# LED_drv.net
KiCad netlist of a schematic drawn in EAGLE
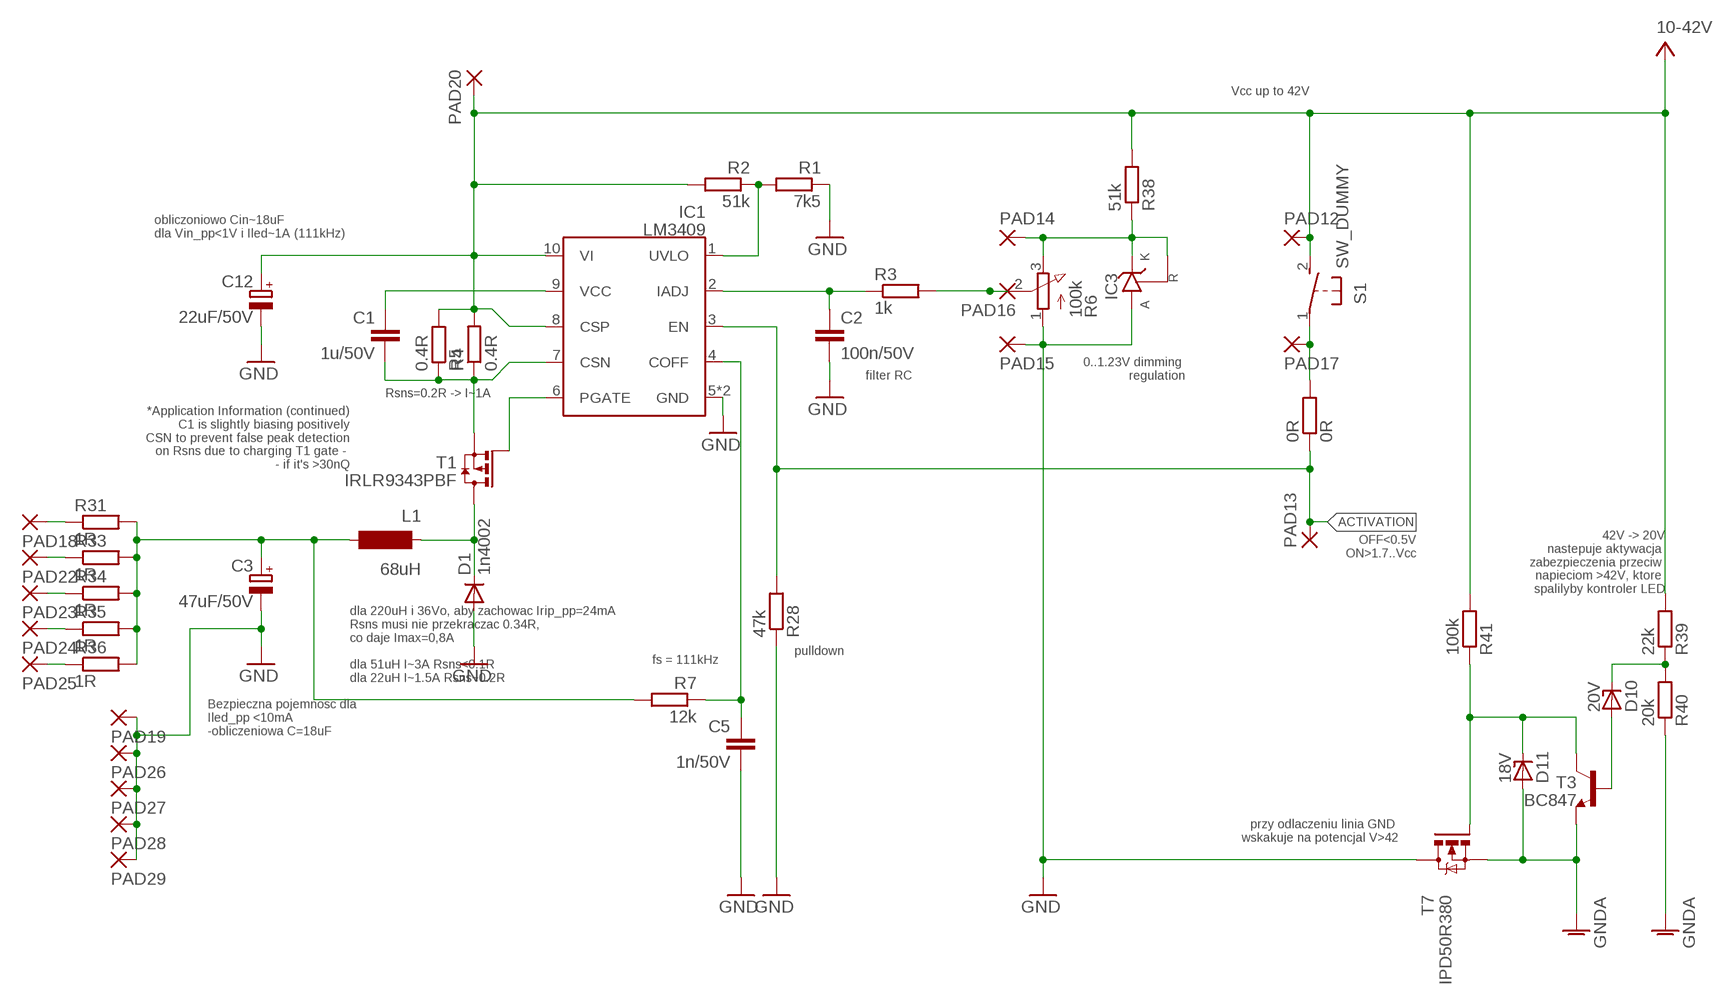
[diagram p0: schematic, sheet 1, part 1 of 2]
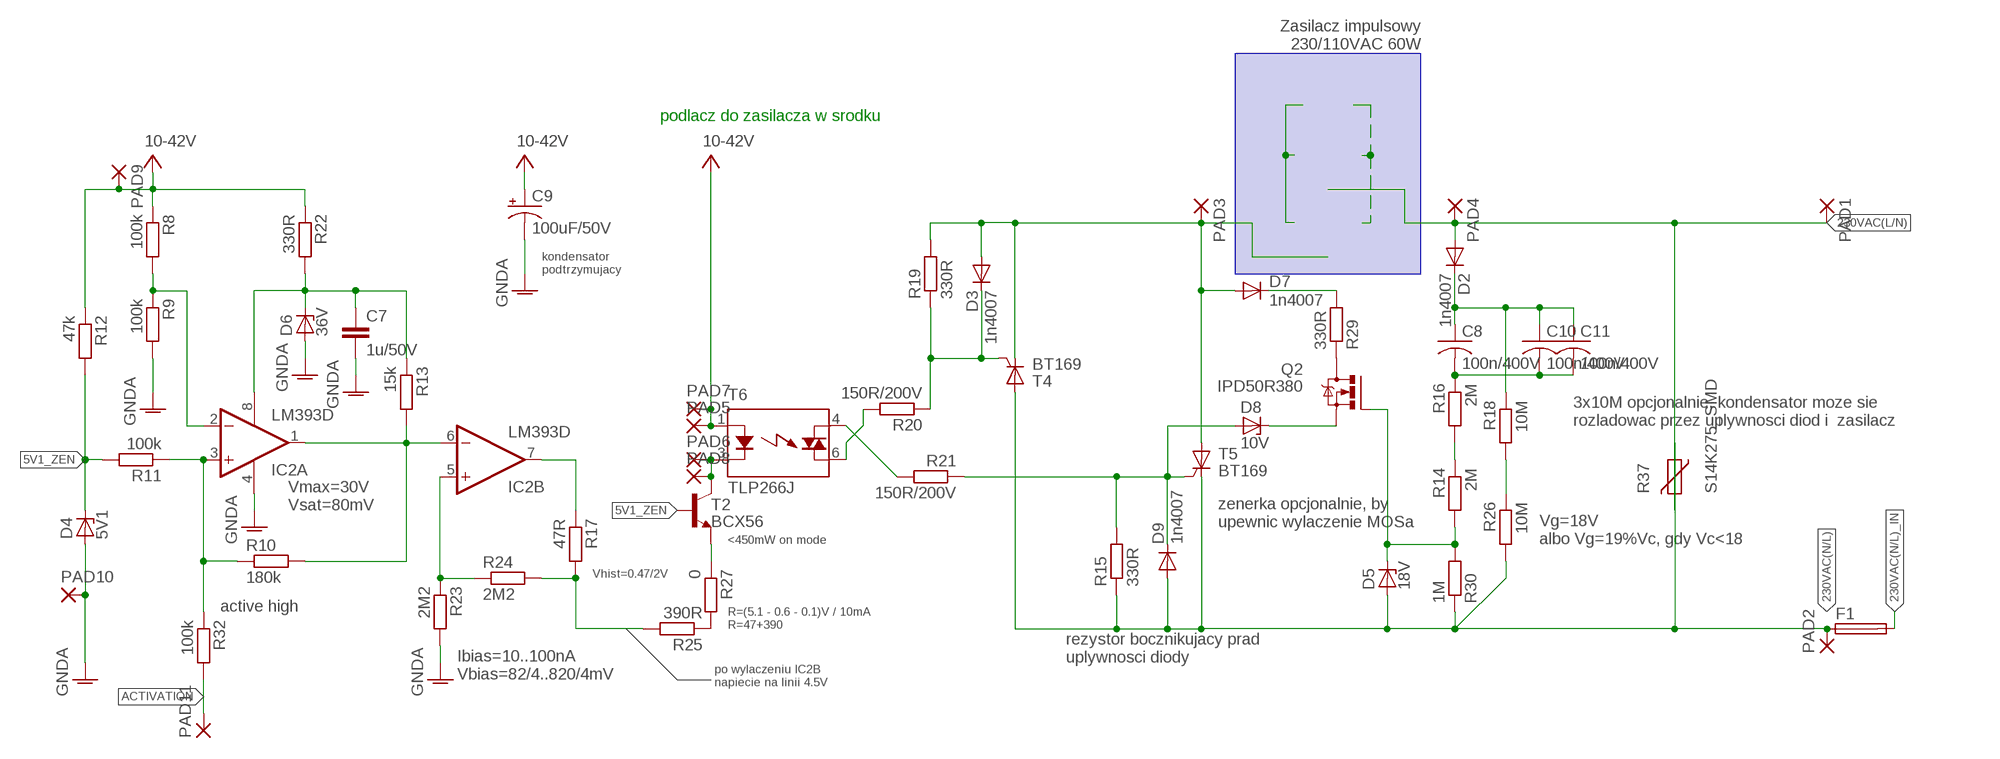
[diagram p1: schematic, sheet 1, part 2 of 2]

(export (version "E")
  (design (tool "Eeschema 10.0.6"))
  (components
    (comp (ref "0R")
      (value "0R")
      (footprint "eagle-import:R1206")
      (libsource (lib "eagle-import") (part "resistor_R-EU_R1206"))
    )
    (comp (ref "C1")
      (value "1u/50V")
      (footprint "eagle-import:C1206")
      (libsource (lib "eagle-import") (part "C-EUC1206"))
    )
    (comp (ref "C2")
      (value "100n/50V")
      (footprint "eagle-import:C0805")
      (libsource (lib "eagle-import") (part "C-EUC0805"))
    )
    (comp (ref "C3")
      (value "47uF/50V")
      (footprint "eagle-import:E5-6")
      (libsource (lib "eagle-import") (part "CPOL-EUE5-6"))
    )
    (comp (ref "C5")
      (value "1n/50V")
      (footprint "eagle-import:C0603")
      (libsource (lib "eagle-import") (part "C-EUC0603"))
    )
    (comp (ref "C7")
      (value "1u/50V")
      (footprint "eagle-import:C1206")
      (libsource (lib "eagle-import") (part "C-EUC1206"))
    )
    (comp (ref "C8")
      (value "100n/400V")
      (footprint "eagle-import:C075-032X103")
      (libsource (lib "eagle-import") (part "C-US075-032X103"))
    )
    (comp (ref "C9")
      (value "100uF/50V")
      (footprint "eagle-import:E3,5-8")
      (libsource (lib "eagle-import") (part "CPOL-USE3.5-8"))
    )
    (comp (ref "C10")
      (value "100n/400V")
      (footprint "eagle-import:C075-032X103")
      (libsource (lib "eagle-import") (part "C-US075-032X103"))
    )
    (comp (ref "C11")
      (value "100n/400V")
      (footprint "eagle-import:C075-032X103")
      (libsource (lib "eagle-import") (part "C-US075-032X103"))
    )
    (comp (ref "C12")
      (value "22uF/50V")
      (footprint "eagle-import:E5-6")
      (libsource (lib "eagle-import") (part "CPOL-EUE5-6"))
    )
    (comp (ref "D1")
      (value "1n4002")
      (footprint "eagle-import:DO214AC")
      (libsource (lib "eagle-import") (part "DIODE-DO214AC"))
    )
    (comp (ref "D2")
      (value "1n4007")
      (footprint "eagle-import:DO-214AC")
      (libsource (lib "eagle-import") (part "DIODE-DO-214AC"))
    )
    (comp (ref "D3")
      (value "1n4007")
      (footprint "eagle-import:DO-214AC")
      (libsource (lib "eagle-import") (part "DIODE-DO-214AC"))
    )
    (comp (ref "D4")
      (value "5V1")
      (footprint "eagle-import:SOD80C")
      (libsource (lib "eagle-import") (part "ZENER-DIODESOD80C"))
    )
    (comp (ref "D5")
      (value "18V")
      (footprint "eagle-import:SOD80C")
      (libsource (lib "eagle-import") (part "ZENER-DIODESOD80C"))
    )
    (comp (ref "D6")
      (value "36V")
      (footprint "eagle-import:SOD80C")
      (libsource (lib "eagle-import") (part "ZENER-DIODESOD80C"))
    )
    (comp (ref "D7")
      (value "1n4007")
      (footprint "eagle-import:DO-214AC")
      (libsource (lib "eagle-import") (part "DIODE-DO-214AC"))
    )
    (comp (ref "D8")
      (value "10V")
      (footprint "eagle-import:SOD80C")
      (libsource (lib "eagle-import") (part "ZENER-DIODESOD80C"))
    )
    (comp (ref "D9")
      (value "1n4007")
      (footprint "eagle-import:DO-214AC")
      (libsource (lib "eagle-import") (part "DIODE-DO-214AC"))
    )
    (comp (ref "D10")
      (value "20V")
      (footprint "eagle-import:SOD80C")
      (libsource (lib "eagle-import") (part "ZENER-DIODESOD80C"))
    )
    (comp (ref "D11")
      (value "18V")
      (footprint "eagle-import:SOD80C")
      (libsource (lib "eagle-import") (part "ZENER-DIODESOD80C"))
    )
    (comp (ref "F1")
      (value "SH22,5A")
      (footprint "eagle-import:SH22,5A")
      (fields (field (name "MPN") "0031.7701.11"))
      (libsource (lib "eagle-import") (part "SH22,5A"))
    )
    (comp (ref "IC1")
      (value "LM3409")
      (footprint "eagle-import:HVSSOP-10")
      (libsource (lib "eagle-import") (part "LM3409"))
    )
    (comp (ref "IC2")
      (value "LM393D")
      (footprint "eagle-import:SO08")
      (libsource (lib "eagle-import") (part "LM393D"))
    )
    (comp (ref "IC3")
      (value "TL431-ASA")
      (footprint "eagle-import:SOT23-3")
      (libsource (lib "eagle-import") (part "TL431-ASA"))
    )
    (comp (ref "L1")
      (value "68uH")
      (footprint "eagle-import:CDRH104-R")
      (libsource (lib "eagle-import") (part "CDRH104R"))
    )
    (comp (ref "PAD1")
      (value "SMD5")
      (footprint "eagle-import:SMD2,54-5,08")
      (libsource (lib "eagle-import") (part "SMD5"))
    )
    (comp (ref "PAD2")
      (value "SMD5")
      (footprint "eagle-import:SMD2,54-5,08")
      (libsource (lib "eagle-import") (part "SMD5"))
    )
    (comp (ref "PAD3")
      (value "SMD5")
      (footprint "eagle-import:SMD2,54-5,08")
      (libsource (lib "eagle-import") (part "SMD5"))
    )
    (comp (ref "PAD4")
      (value "SMD5")
      (footprint "eagle-import:SMD2,54-5,08")
      (libsource (lib "eagle-import") (part "SMD5"))
    )
    (comp (ref "PAD5")
      (value "SMD2")
      (footprint "eagle-import:SMD1,27-2,54")
      (libsource (lib "eagle-import") (part "SMD2"))
    )
    (comp (ref "PAD6")
      (value "SMD2")
      (footprint "eagle-import:SMD1,27-2,54")
      (libsource (lib "eagle-import") (part "SMD2"))
    )
    (comp (ref "PAD7")
      (value "SMD2")
      (footprint "eagle-import:SMD1,27-2,54")
      (libsource (lib "eagle-import") (part "SMD2"))
    )
    (comp (ref "PAD8")
      (value "SMD2")
      (footprint "eagle-import:SMD1,27-2,54")
      (libsource (lib "eagle-import") (part "SMD2"))
    )
    (comp (ref "PAD9")
      (value "SMD2")
      (footprint "eagle-import:SMD1,27-2,54")
      (libsource (lib "eagle-import") (part "SMD2"))
    )
    (comp (ref "PAD10")
      (value "SMD2")
      (footprint "eagle-import:SMD1,27-2,54")
      (libsource (lib "eagle-import") (part "SMD2"))
    )
    (comp (ref "PAD11")
      (value "SMD2")
      (footprint "eagle-import:SMD1,27-2,54")
      (libsource (lib "eagle-import") (part "SMD2"))
    )
    (comp (ref "PAD12")
      (value "SMD2")
      (footprint "eagle-import:SMD1,27-2,54")
      (libsource (lib "eagle-import") (part "SMD2"))
    )
    (comp (ref "PAD13")
      (value "SMD2")
      (footprint "eagle-import:SMD1,27-2,54")
      (libsource (lib "eagle-import") (part "SMD2"))
    )
    (comp (ref "PAD14")
      (value "SMD2")
      (footprint "eagle-import:SMD1,27-2,54")
      (libsource (lib "eagle-import") (part "SMD2"))
    )
    (comp (ref "PAD15")
      (value "SMD2")
      (footprint "eagle-import:SMD1,27-2,54")
      (libsource (lib "eagle-import") (part "SMD2"))
    )
    (comp (ref "PAD16")
      (value "SMD2")
      (footprint "eagle-import:SMD1,27-2,54")
      (libsource (lib "eagle-import") (part "SMD2"))
    )
    (comp (ref "PAD17")
      (value "SMD2")
      (footprint "eagle-import:SMD1,27-2,54")
      (libsource (lib "eagle-import") (part "SMD2"))
    )
    (comp (ref "PAD18")
      (value "SMD2")
      (footprint "eagle-import:SMD1,27-2,54")
      (libsource (lib "eagle-import") (part "SMD2"))
    )
    (comp (ref "PAD19")
      (value "SMD2")
      (footprint "eagle-import:SMD1,27-2,54")
      (libsource (lib "eagle-import") (part "SMD2"))
    )
    (comp (ref "PAD20")
      (value "SMD2")
      (footprint "eagle-import:SMD1,27-2,54")
      (libsource (lib "eagle-import") (part "SMD2"))
    )
    (comp (ref "PAD22")
      (value "SMD2")
      (footprint "eagle-import:SMD1,27-2,54")
      (libsource (lib "eagle-import") (part "SMD2"))
    )
    (comp (ref "PAD23")
      (value "SMD2")
      (footprint "eagle-import:SMD1,27-2,54")
      (libsource (lib "eagle-import") (part "SMD2"))
    )
    (comp (ref "PAD24")
      (value "SMD2")
      (footprint "eagle-import:SMD1,27-2,54")
      (libsource (lib "eagle-import") (part "SMD2"))
    )
    (comp (ref "PAD25")
      (value "SMD2")
      (footprint "eagle-import:SMD1,27-2,54")
      (libsource (lib "eagle-import") (part "SMD2"))
    )
    (comp (ref "PAD26")
      (value "SMD2")
      (footprint "eagle-import:SMD1,27-2,54")
      (libsource (lib "eagle-import") (part "SMD2"))
    )
    (comp (ref "PAD27")
      (value "SMD2")
      (footprint "eagle-import:SMD1,27-2,54")
      (libsource (lib "eagle-import") (part "SMD2"))
    )
    (comp (ref "PAD28")
      (value "SMD2")
      (footprint "eagle-import:SMD1,27-2,54")
      (libsource (lib "eagle-import") (part "SMD2"))
    )
    (comp (ref "PAD29")
      (value "SMD2")
      (footprint "eagle-import:SMD1,27-2,54")
      (libsource (lib "eagle-import") (part "SMD2"))
    )
    (comp (ref "Q2")
      (value "IPD50R380")
      (footprint "eagle-import:TO252-3-11")
      (libsource (lib "eagle-import") (part "IPD50R380"))
    )
    (comp (ref "R1")
      (value "7k5")
      (footprint "eagle-import:R1206")
      (libsource (lib "eagle-import") (part "R-EU_R1206"))
    )
    (comp (ref "R2")
      (value "51k")
      (footprint "eagle-import:R1206")
      (libsource (lib "eagle-import") (part "R-EU_R1206"))
    )
    (comp (ref "R3")
      (value "1k")
      (footprint "eagle-import:R0805")
      (libsource (lib "eagle-import") (part "R-EU_R0805"))
    )
    (comp (ref "R4")
      (value "0.4R")
      (footprint "eagle-import:R1206")
      (libsource (lib "eagle-import") (part "resistor_R-EU_R1206"))
    )
    (comp (ref "R5")
      (value "0.4R")
      (footprint "eagle-import:R1206")
      (libsource (lib "eagle-import") (part "resistor_R-EU_R1206"))
    )
    (comp (ref "R6")
      (value "100k")
      (footprint "eagle-import:3RP_1610N")
      (libsource (lib "eagle-import") (part "3RP/1610N"))
    )
    (comp (ref "R7")
      (value "12k")
      (footprint "eagle-import:R1206")
      (libsource (lib "eagle-import") (part "R-EU_R1206"))
    )
    (comp (ref "R8")
      (value "100k")
      (footprint "eagle-import:R0805")
      (libsource (lib "eagle-import") (part "resistor_R-EU_R0805"))
    )
    (comp (ref "R9")
      (value "100k")
      (footprint "eagle-import:R1206")
      (libsource (lib "eagle-import") (part "R-EU_R1206"))
    )
    (comp (ref "R10")
      (value "180k")
      (footprint "eagle-import:R1206")
      (libsource (lib "eagle-import") (part "R-EU_R1206"))
    )
    (comp (ref "R11")
      (value "100k")
      (footprint "eagle-import:R0805")
      (libsource (lib "eagle-import") (part "resistor_R-EU_R0805"))
    )
    (comp (ref "R12")
      (value "47k")
      (footprint "eagle-import:R0805")
      (libsource (lib "eagle-import") (part "resistor_R-EU_R0805"))
    )
    (comp (ref "R13")
      (value "15k")
      (footprint "eagle-import:R0805")
      (libsource (lib "eagle-import") (part "resistor_R-EU_R0805"))
    )
    (comp (ref "R14")
      (value "2M")
      (footprint "eagle-import:R1206")
      (libsource (lib "eagle-import") (part "R-EU_R1206"))
    )
    (comp (ref "R15")
      (value "330R")
      (footprint "eagle-import:R1206")
      (libsource (lib "eagle-import") (part "R-EU_R1206"))
    )
    (comp (ref "R16")
      (value "2M")
      (footprint "eagle-import:R1206")
      (libsource (lib "eagle-import") (part "R-EU_R1206"))
    )
    (comp (ref "R17")
      (value "47R")
      (footprint "eagle-import:R0805")
      (libsource (lib "eagle-import") (part "resistor_R-EU_R0805"))
    )
    (comp (ref "R18")
      (value "10M")
      (footprint "eagle-import:R1206")
      (libsource (lib "eagle-import") (part "R-EU_R1206"))
    )
    (comp (ref "R19")
      (value "330R")
      (footprint "eagle-import:R1206")
      (libsource (lib "eagle-import") (part "R-EU_R1206"))
    )
    (comp (ref "R20")
      (value "150R/200V")
      (footprint "eagle-import:R1206")
      (libsource (lib "eagle-import") (part "R-EU_R1206"))
    )
    (comp (ref "R21")
      (value "150R/200V")
      (footprint "eagle-import:R1206")
      (libsource (lib "eagle-import") (part "R-EU_R1206"))
    )
    (comp (ref "R22")
      (value "330R")
      (footprint "eagle-import:R0805")
      (libsource (lib "eagle-import") (part "resistor_R-EU_R0805"))
    )
    (comp (ref "R23")
      (value "2M2")
      (footprint "eagle-import:R0805")
      (libsource (lib "eagle-import") (part "resistor_R-EU_R0805"))
    )
    (comp (ref "R24")
      (value "2M2")
      (footprint "eagle-import:R0805")
      (libsource (lib "eagle-import") (part "resistor_R-EU_R0805"))
    )
    (comp (ref "R25")
      (value "390R")
      (footprint "eagle-import:R0805")
      (libsource (lib "eagle-import") (part "resistor_R-EU_R0805"))
    )
    (comp (ref "R26")
      (value "10M")
      (footprint "eagle-import:R1206")
      (libsource (lib "eagle-import") (part "R-EU_R1206"))
    )
    (comp (ref "R27")
      (value "0")
      (footprint "eagle-import:R1206")
      (libsource (lib "eagle-import") (part "R-EU_R1206"))
    )
    (comp (ref "R28")
      (value "47k")
      (footprint "eagle-import:R0805")
      (libsource (lib "eagle-import") (part "R-EU_R0805"))
    )
    (comp (ref "R29")
      (value "330R")
      (footprint "eagle-import:R1206")
      (libsource (lib "eagle-import") (part "R-EU_R1206"))
    )
    (comp (ref "R30")
      (value "1M")
      (footprint "eagle-import:R1206")
      (libsource (lib "eagle-import") (part "R-EU_R1206"))
    )
    (comp (ref "R31")
      (value "1R")
      (footprint "eagle-import:R1206")
      (libsource (lib "eagle-import") (part "resistor_R-EU_R1206"))
    )
    (comp (ref "R32")
      (value "100k")
      (footprint "eagle-import:R0805")
      (libsource (lib "eagle-import") (part "resistor_R-EU_R0805"))
    )
    (comp (ref "R33")
      (value "1R")
      (footprint "eagle-import:R1206")
      (libsource (lib "eagle-import") (part "resistor_R-EU_R1206"))
    )
    (comp (ref "R34")
      (value "1R")
      (footprint "eagle-import:R1206")
      (libsource (lib "eagle-import") (part "resistor_R-EU_R1206"))
    )
    (comp (ref "R35")
      (value "1R")
      (footprint "eagle-import:R1206")
      (libsource (lib "eagle-import") (part "resistor_R-EU_R1206"))
    )
    (comp (ref "R36")
      (value "1R")
      (footprint "eagle-import:R1206")
      (libsource (lib "eagle-import") (part "resistor_R-EU_R1206"))
    )
    (comp (ref "R37")
      (value "S14K275_SMD")
      (footprint "eagle-import:S14K275_SMD")
      (libsource (lib "eagle-import") (part "S14K275_SMD"))
    )
    (comp (ref "R38")
      (value "51k")
      (footprint "eagle-import:R1206")
      (libsource (lib "eagle-import") (part "R-EU_R1206"))
    )
    (comp (ref "R39")
      (value "22k")
      (footprint "eagle-import:R1206")
      (libsource (lib "eagle-import") (part "R-EU_R1206"))
    )
    (comp (ref "R40")
      (value "20k")
      (footprint "eagle-import:R1206")
      (libsource (lib "eagle-import") (part "R-EU_R1206"))
    )
    (comp (ref "R41")
      (value "100k")
      (footprint "eagle-import:R1206")
      (libsource (lib "eagle-import") (part "R-EU_R1206"))
    )
    (comp (ref "S1")
      (value "SW_DUMMY")
      (footprint "eagle-import:SW_DUMMY")
      (libsource (lib "eagle-import") (part "SW_DUMMY"))
    )
    (comp (ref "T1")
      (value "IRLR9343PBF")
      (footprint "eagle-import:TO252-3-11")
      (libsource (lib "eagle-import") (part "IRLR9343PBF"))
    )
    (comp (ref "T2")
      (value "BCX56")
      (footprint "eagle-import:SOT89")
      (libsource (lib "eagle-import") (part "BCX56"))
    )
    (comp (ref "T3")
      (value "BC847")
      (footprint "eagle-import:SOT23")
      (libsource (lib "eagle-import") (part "BC847"))
    )
    (comp (ref "T4")
      (value "BT169")
      (footprint "eagle-import:SOT223")
      (libsource (lib "eagle-import") (part "BT169"))
    )
    (comp (ref "T5")
      (value "BT169")
      (footprint "eagle-import:SOT223")
      (libsource (lib "eagle-import") (part "BT169"))
    )
    (comp (ref "T6")
      (value "TLP266J")
      (footprint "eagle-import:SO6")
      (libsource (lib "eagle-import") (part "TLP266J"))
    )
    (comp (ref "T7")
      (value "IPD50R380")
      (footprint "eagle-import:TO252-3-11")
      (libsource (lib "eagle-import") (part "IPD50R380"))
    )
  )
  (nets
    (net (code "1") (name "5V1_ZEN") (class "Default")
      (node (ref "D4") (pin "C") (pinfunction "C_C") (pintype "passive"))
      (node (ref "R11") (pin "2") (pinfunction "2_2") (pintype "passive"))
      (node (ref "R12") (pin "2") (pinfunction "2_2") (pintype "passive"))
      (node (ref "T2") (pin "B") (pinfunction "B_B") (pintype "passive"))
    )
    (net (code "2") (name "10-42V") (class "Default")
      (node (ref "C12") (pin "+") (pinfunction "+_+") (pintype "passive"))
      (node (ref "C9") (pin "+") (pinfunction "+_+") (pintype "passive"))
      (node (ref "IC1") (pin "10") (pinfunction "VI_10") (pintype "output"))
      (node (ref "IC1") (pin "8") (pinfunction "CSP_8") (pintype "passive"))
      (node (ref "PAD12") (pin "1") (pinfunction "P_1") (pintype "passive"))
      (node (ref "PAD20") (pin "1") (pinfunction "P_1") (pintype "passive"))
      (node (ref "PAD5") (pin "1") (pinfunction "P_1") (pintype "passive"))
      (node (ref "PAD7") (pin "1") (pinfunction "P_1") (pintype "passive"))
      (node (ref "PAD9") (pin "1") (pinfunction "P_1") (pintype "passive"))
      (node (ref "R12") (pin "1") (pinfunction "1_1") (pintype "passive"))
      (node (ref "R2") (pin "2") (pinfunction "2_2") (pintype "passive"))
      (node (ref "R22") (pin "1") (pinfunction "1_1") (pintype "passive"))
      (node (ref "R38") (pin "2") (pinfunction "2_2") (pintype "passive"))
      (node (ref "R39") (pin "2") (pinfunction "2_2") (pintype "passive"))
      (node (ref "R4") (pin "2") (pinfunction "2_2") (pintype "passive"))
      (node (ref "R41") (pin "2") (pinfunction "2_2") (pintype "passive"))
      (node (ref "R5") (pin "2") (pinfunction "2_2") (pintype "passive"))
      (node (ref "R8") (pin "1") (pinfunction "1_1") (pintype "passive"))
      (node (ref "S1") (pin "2") (pinfunction "S_2") (pintype "passive"))
      (node (ref "T6") (pin "1") (pinfunction "A_1") (pintype "passive"))
    )
    (net (code "3") (name "230VAC(L{slash}N)") (class "Default")
      (node (ref "D2") (pin "A") (pinfunction "A_A") (pintype "passive"))
      (node (ref "PAD1") (pin "1") (pinfunction "P_1") (pintype "passive"))
      (node (ref "PAD4") (pin "1") (pinfunction "P_1") (pintype "passive"))
      (node (ref "R37") (pin "2") (pinfunction "2_2") (pintype "passive"))
    )
    (net (code "4") (name "230VAC(N{slash}L)") (class "Default")
      (node (ref "D5") (pin "A") (pinfunction "A_A") (pintype "passive"))
      (node (ref "D9") (pin "A") (pinfunction "A_A") (pintype "passive"))
      (node (ref "F1") (pin "1") (pinfunction "1_1") (pintype "passive"))
      (node (ref "PAD2") (pin "1") (pinfunction "P_1") (pintype "passive"))
      (node (ref "R15") (pin "1") (pinfunction "1_1") (pintype "passive"))
      (node (ref "R26") (pin "2") (pinfunction "2_2") (pintype "passive"))
      (node (ref "R30") (pin "1") (pinfunction "1_1") (pintype "passive"))
      (node (ref "R37") (pin "1") (pinfunction "1_1") (pintype "passive"))
      (node (ref "T4") (pin "2") (pinfunction "A_2") (pintype "passive"))
      (node (ref "T4") (pin "4") (pinfunction "A_4") (pintype "passive"))
      (node (ref "T5") (pin "3") (pinfunction "C_3") (pintype "passive"))
    )
    (net (code "5") (name "230VAC(N{slash}L)_IN") (class "Default")
      (node (ref "F1") (pin "2") (pinfunction "2_2") (pintype "passive"))
    )
    (net (code "6") (name "ACTIVATION") (class "Default")
      (node (ref "0R") (pin "1") (pinfunction "1_1") (pintype "passive"))
      (node (ref "IC1") (pin "3") (pinfunction "EN_3") (pintype "power_in"))
      (node (ref "PAD11") (pin "1") (pinfunction "P_1") (pintype "passive"))
      (node (ref "PAD13") (pin "1") (pinfunction "P_1") (pintype "passive"))
      (node (ref "R28") (pin "2") (pinfunction "2_2") (pintype "passive"))
      (node (ref "R32") (pin "2") (pinfunction "2_2") (pintype "passive"))
    )
    (net (code "7") (name "GND") (class "Default")
      (node (ref "C12") (pin "-") (pinfunction "-_-") (pintype "passive"))
      (node (ref "C2") (pin "2") (pinfunction "2_2") (pintype "passive"))
      (node (ref "C3") (pin "-") (pinfunction "-_-") (pintype "passive"))
      (node (ref "C5") (pin "2") (pinfunction "2_2") (pintype "passive"))
      (node (ref "D1") (pin "A") (pinfunction "A_A") (pintype "passive"))
      (node (ref "IC1") (pin "5") (pinfunction "GND_5") (pintype "bidirectional"))
      (node (ref "IC1") (pin "EXT") (pinfunction "GND_EXT") (pintype "bidirectional"))
      (node (ref "IC3") (pin "3") (pinfunction "A_3") (pintype "bidirectional"))
      (node (ref "PAD15") (pin "1") (pinfunction "P_1") (pintype "passive"))
      (node (ref "PAD19") (pin "1") (pinfunction "P_1") (pintype "passive"))
      (node (ref "PAD26") (pin "1") (pinfunction "P_1") (pintype "passive"))
      (node (ref "PAD27") (pin "1") (pinfunction "P_1") (pintype "passive"))
      (node (ref "PAD28") (pin "1") (pinfunction "P_1") (pintype "passive"))
      (node (ref "PAD29") (pin "1") (pinfunction "P_1") (pintype "passive"))
      (node (ref "R1") (pin "1") (pinfunction "1_1") (pintype "passive"))
      (node (ref "R28") (pin "1") (pinfunction "1_1") (pintype "passive"))
      (node (ref "R6") (pin "1") (pinfunction "A_1") (pintype "passive"))
      (node (ref "T7") (pin "2") (pinfunction "D_2") (pintype "passive"))
    )
    (net (code "8") (name "GNDA") (class "Default")
      (node (ref "C7") (pin "2") (pinfunction "2_2") (pintype "passive"))
      (node (ref "C9") (pin "-") (pinfunction "-_-") (pintype "passive"))
      (node (ref "D11") (pin "A") (pinfunction "A_A") (pintype "passive"))
      (node (ref "D4") (pin "A") (pinfunction "A_A") (pintype "passive"))
      (node (ref "D6") (pin "A") (pinfunction "A_A") (pintype "passive"))
      (node (ref "IC2") (pin "4") (pinfunction "V-_4") (pintype "power_in"))
      (node (ref "PAD10") (pin "1") (pinfunction "P_1") (pintype "passive"))
      (node (ref "R23") (pin "2") (pinfunction "2_2") (pintype "passive"))
      (node (ref "R40") (pin "1") (pinfunction "1_1") (pintype "passive"))
      (node (ref "R9") (pin "2") (pinfunction "2_2") (pintype "passive"))
      (node (ref "T3") (pin "2") (pinfunction "E_2") (pintype "passive"))
      (node (ref "T7") (pin "3") (pinfunction "S_3") (pintype "passive"))
    )
    (net (code "9") (name "Net-(C3-Pad+)") (class "Default")
      (node (ref "C3") (pin "+") (pinfunction "+_+") (pintype "passive"))
      (node (ref "L1") (pin "2") (pinfunction "2_2") (pintype "passive"))
      (node (ref "R31") (pin "2") (pinfunction "2_2") (pintype "passive"))
      (node (ref "R33") (pin "2") (pinfunction "2_2") (pintype "passive"))
      (node (ref "R34") (pin "2") (pinfunction "2_2") (pintype "passive"))
      (node (ref "R35") (pin "2") (pinfunction "2_2") (pintype "passive"))
      (node (ref "R36") (pin "2") (pinfunction "2_2") (pintype "passive"))
      (node (ref "R7") (pin "2") (pinfunction "2_2") (pintype "passive"))
    )
    (net (code "10") (name "Net-(C10-Pad1)") (class "Default")
      (node (ref "C10") (pin "1") (pinfunction "1_1") (pintype "passive"))
      (node (ref "C11") (pin "1") (pinfunction "1_1") (pintype "passive"))
      (node (ref "C8") (pin "1") (pinfunction "1_1") (pintype "passive"))
      (node (ref "D2") (pin "C") (pinfunction "C_C") (pintype "passive"))
      (node (ref "R18") (pin "1") (pinfunction "1_1") (pintype "passive"))
    )
    (net (code "11") (name "Net-(C10-Pad2)") (class "Default")
      (node (ref "C10") (pin "2") (pinfunction "2_2") (pintype "passive"))
      (node (ref "C11") (pin "2") (pinfunction "2_2") (pintype "passive"))
      (node (ref "C8") (pin "2") (pinfunction "2_2") (pintype "passive"))
      (node (ref "R16") (pin "1") (pinfunction "1_1") (pintype "passive"))
    )
    (net (code "12") (name "Net-(D7-PadC)") (class "Default")
      (node (ref "D7") (pin "C") (pinfunction "C_C") (pintype "passive"))
      (node (ref "R29") (pin "2") (pinfunction "2_2") (pintype "passive"))
    )
    (net (code "13") (name "Net-(D10-PadC)") (class "Default")
      (node (ref "D10") (pin "C") (pinfunction "C_C") (pintype "passive"))
      (node (ref "R39") (pin "1") (pinfunction "1_1") (pintype "passive"))
      (node (ref "R40") (pin "2") (pinfunction "2_2") (pintype "passive"))
    )
    (net (code "14") (name "Net-(IC1-COFF)") (class "Default")
      (node (ref "C5") (pin "1") (pinfunction "1_1") (pintype "passive"))
      (node (ref "IC1") (pin "4") (pinfunction "COFF_4") (pintype "power_in"))
      (node (ref "R7") (pin "1") (pinfunction "1_1") (pintype "passive"))
    )
    (net (code "15") (name "Net-(IC1-CSN)") (class "Default")
      (node (ref "C1") (pin "2") (pinfunction "2_2") (pintype "passive"))
      (node (ref "IC1") (pin "7") (pinfunction "CSN_7") (pintype "passive"))
      (node (ref "R4") (pin "1") (pinfunction "1_1") (pintype "passive"))
      (node (ref "R5") (pin "1") (pinfunction "1_1") (pintype "passive"))
      (node (ref "T1") (pin "2") (pinfunction "S_2") (pintype "passive"))
    )
    (net (code "16") (name "Net-(IC1-IADJ)") (class "Default")
      (node (ref "C2") (pin "1") (pinfunction "1_1") (pintype "passive"))
      (node (ref "IC1") (pin "2") (pinfunction "IADJ_2") (pintype "input"))
      (node (ref "R3") (pin "1") (pinfunction "1_1") (pintype "passive"))
    )
    (net (code "17") (name "Net-(IC1-PGATE)") (class "Default")
      (node (ref "IC1") (pin "6") (pinfunction "PGATE_6") (pintype "bidirectional"))
      (node (ref "T1") (pin "1") (pinfunction "G_1") (pintype "passive"))
    )
    (net (code "18") (name "Net-(IC1-UVLO)") (class "Default")
      (node (ref "IC1") (pin "1") (pinfunction "UVLO_1") (pintype "input"))
      (node (ref "R1") (pin "2") (pinfunction "2_2") (pintype "passive"))
      (node (ref "R2") (pin "1") (pinfunction "1_1") (pintype "passive"))
    )
    (net (code "19") (name "Net-(IC1-VCC)") (class "Default")
      (node (ref "C1") (pin "1") (pinfunction "1_1") (pintype "passive"))
      (node (ref "IC1") (pin "9") (pinfunction "VCC_9") (pintype "passive"))
    )
    (net (code "20") (name "Net-(IC2A-+IN)") (class "Default")
      (node (ref "IC2") (pin "3") (pinfunction "+IN_3") (pintype "input"))
      (node (ref "R10") (pin "1") (pinfunction "1_1") (pintype "passive"))
      (node (ref "R11") (pin "1") (pinfunction "1_1") (pintype "passive"))
      (node (ref "R32") (pin "1") (pinfunction "1_1") (pintype "passive"))
    )
    (net (code "21") (name "Net-(IC2A--IN)") (class "Default")
      (node (ref "IC2") (pin "2") (pinfunction "-IN_2") (pintype "input"))
      (node (ref "R8") (pin "2") (pinfunction "2_2") (pintype "passive"))
      (node (ref "R9") (pin "1") (pinfunction "1_1") (pintype "passive"))
    )
    (net (code "22") (name "Net-(IC2A-OUT)") (class "Default")
      (node (ref "IC2") (pin "1") (pinfunction "OUT_1") (pintype "output"))
      (node (ref "IC2") (pin "6") (pinfunction "-IN_6") (pintype "input"))
      (node (ref "R10") (pin "2") (pinfunction "2_2") (pintype "passive"))
      (node (ref "R13") (pin "2") (pinfunction "2_2") (pintype "passive"))
    )
    (net (code "23") (name "Net-(IC2B-+IN)") (class "Default")
      (node (ref "IC2") (pin "5") (pinfunction "+IN_5") (pintype "input"))
      (node (ref "R23") (pin "1") (pinfunction "1_1") (pintype "passive"))
      (node (ref "R24") (pin "1") (pinfunction "1_1") (pintype "passive"))
    )
    (net (code "24") (name "Net-(IC2B-OUT)") (class "Default")
      (node (ref "IC2") (pin "7") (pinfunction "OUT_7") (pintype "output"))
      (node (ref "R17") (pin "1") (pinfunction "1_1") (pintype "passive"))
    )
    (net (code "25") (name "Net-(IC2C-V+)") (class "Default")
      (node (ref "C7") (pin "1") (pinfunction "1_1") (pintype "passive"))
      (node (ref "D6") (pin "C") (pinfunction "C_C") (pintype "passive"))
      (node (ref "IC2") (pin "8") (pinfunction "V+_8") (pintype "power_in"))
      (node (ref "R13") (pin "1") (pinfunction "1_1") (pintype "passive"))
      (node (ref "R22") (pin "2") (pinfunction "2_2") (pintype "passive"))
    )
    (net (code "26") (name "Net-(IC3-K)") (class "Default")
      (node (ref "IC3") (pin "1") (pinfunction "R_1") (pintype "bidirectional"))
      (node (ref "IC3") (pin "2") (pinfunction "K_2") (pintype "bidirectional"))
      (node (ref "PAD14") (pin "1") (pinfunction "P_1") (pintype "passive"))
      (node (ref "R38") (pin "1") (pinfunction "1_1") (pintype "passive"))
      (node (ref "R6") (pin "3") (pinfunction "E_3") (pintype "passive"))
    )
    (net (code "27") (name "Net-(PAD3-P)") (class "Default")
      (node (ref "D3") (pin "A") (pinfunction "A_A") (pintype "passive"))
      (node (ref "D7") (pin "A") (pinfunction "A_A") (pintype "passive"))
      (node (ref "PAD3") (pin "1") (pinfunction "P_1") (pintype "passive"))
      (node (ref "R19") (pin "2") (pinfunction "2_2") (pintype "passive"))
      (node (ref "T4") (pin "3") (pinfunction "C_3") (pintype "passive"))
      (node (ref "T5") (pin "2") (pinfunction "A_2") (pintype "passive"))
      (node (ref "T5") (pin "4") (pinfunction "A_4") (pintype "passive"))
    )
    (net (code "28") (name "Net-(PAD6-P)") (class "Default")
      (node (ref "PAD6") (pin "1") (pinfunction "P_1") (pintype "passive"))
      (node (ref "PAD8") (pin "1") (pinfunction "P_1") (pintype "passive"))
      (node (ref "T2") (pin "C") (pinfunction "C_C") (pintype "passive"))
      (node (ref "T2") (pin "C@1") (pinfunction "C_C@1") (pintype "passive"))
      (node (ref "T6") (pin "3") (pinfunction "K_3") (pintype "passive"))
    )
    (net (code "29") (name "Net-(PAD16-P)") (class "Default")
      (node (ref "PAD16") (pin "1") (pinfunction "P_1") (pintype "passive"))
      (node (ref "R3") (pin "2") (pinfunction "2_2") (pintype "passive"))
      (node (ref "R6") (pin "2") (pinfunction "S_2") (pintype "passive"))
    )
    (net (code "30") (name "Net-(PAD17-P)") (class "Default")
      (node (ref "0R") (pin "2") (pinfunction "2_2") (pintype "passive"))
      (node (ref "PAD17") (pin "1") (pinfunction "P_1") (pintype "passive"))
      (node (ref "S1") (pin "1") (pinfunction "P_1") (pintype "passive"))
    )
    (net (code "31") (name "Net-(PAD18-P)") (class "Default")
      (node (ref "PAD18") (pin "1") (pinfunction "P_1") (pintype "passive"))
      (node (ref "R31") (pin "1") (pinfunction "1_1") (pintype "passive"))
    )
    (net (code "32") (name "Net-(PAD22-P)") (class "Default")
      (node (ref "PAD22") (pin "1") (pinfunction "P_1") (pintype "passive"))
      (node (ref "R33") (pin "1") (pinfunction "1_1") (pintype "passive"))
    )
    (net (code "33") (name "Net-(PAD23-P)") (class "Default")
      (node (ref "PAD23") (pin "1") (pinfunction "P_1") (pintype "passive"))
      (node (ref "R34") (pin "1") (pinfunction "1_1") (pintype "passive"))
    )
    (net (code "34") (name "Net-(PAD24-P)") (class "Default")
      (node (ref "PAD24") (pin "1") (pinfunction "P_1") (pintype "passive"))
      (node (ref "R35") (pin "1") (pinfunction "1_1") (pintype "passive"))
    )
    (net (code "35") (name "Net-(PAD25-P)") (class "Default")
      (node (ref "PAD25") (pin "1") (pinfunction "P_1") (pintype "passive"))
      (node (ref "R36") (pin "1") (pinfunction "1_1") (pintype "passive"))
    )
    (net (code "36") (name "Net-(Q2-D)") (class "Default")
      (node (ref "Q2") (pin "2") (pinfunction "D_2") (pintype "passive"))
      (node (ref "R29") (pin "1") (pinfunction "1_1") (pintype "passive"))
    )
    (net (code "37") (name "Net-(Q2-G)") (class "Default")
      (node (ref "D5") (pin "C") (pinfunction "C_C") (pintype "passive"))
      (node (ref "Q2") (pin "1") (pinfunction "G_1") (pintype "passive"))
      (node (ref "R14") (pin "2") (pinfunction "2_2") (pintype "passive"))
      (node (ref "R30") (pin "2") (pinfunction "2_2") (pintype "passive"))
    )
    (net (code "38") (name "Net-(Q2-S)") (class "Default")
      (node (ref "D8") (pin "C") (pinfunction "C_C") (pintype "passive"))
      (node (ref "Q2") (pin "3") (pinfunction "S_3") (pintype "passive"))
    )
    (net (code "39") (name "Net-(R14-Pad1)") (class "Default")
      (node (ref "R14") (pin "1") (pinfunction "1_1") (pintype "passive"))
      (node (ref "R16") (pin "2") (pinfunction "2_2") (pintype "passive"))
    )
    (net (code "40") (name "Net-(R17-Pad2)") (class "Default")
      (node (ref "R17") (pin "2") (pinfunction "2_2") (pintype "passive"))
      (node (ref "R24") (pin "2") (pinfunction "2_2") (pintype "passive"))
      (node (ref "R25") (pin "2") (pinfunction "2_2") (pintype "passive"))
    )
    (net (code "41") (name "Net-(R18-Pad2)") (class "Default")
      (node (ref "R18") (pin "2") (pinfunction "2_2") (pintype "passive"))
      (node (ref "R26") (pin "1") (pinfunction "1_1") (pintype "passive"))
    )
    (net (code "42") (name "Net-(R25-Pad1)") (class "Default")
      (node (ref "R25") (pin "1") (pinfunction "1_1") (pintype "passive"))
      (node (ref "R27") (pin "2") (pinfunction "2_2") (pintype "passive"))
    )
    (net (code "43") (name "Net-(R27-Pad1)") (class "Default")
      (node (ref "R27") (pin "1") (pinfunction "1_1") (pintype "passive"))
      (node (ref "T2") (pin "E") (pinfunction "E_E") (pintype "passive"))
    )
    (net (code "44") (name "Net-(T1-D)") (class "Default")
      (node (ref "D1") (pin "C") (pinfunction "C_C") (pintype "passive"))
      (node (ref "L1") (pin "1") (pinfunction "1_1") (pintype "passive"))
      (node (ref "T1") (pin "3") (pinfunction "D_3") (pintype "passive"))
    )
    (net (code "45") (name "Net-(T3-B)") (class "Default")
      (node (ref "D10") (pin "A") (pinfunction "A_A") (pintype "passive"))
      (node (ref "T3") (pin "1") (pinfunction "B_1") (pintype "passive"))
    )
    (net (code "46") (name "Net-(T3-C)") (class "Default")
      (node (ref "D11") (pin "C") (pinfunction "C_C") (pintype "passive"))
      (node (ref "R41") (pin "1") (pinfunction "1_1") (pintype "passive"))
      (node (ref "T3") (pin "3") (pinfunction "C_3") (pintype "passive"))
      (node (ref "T7") (pin "1") (pinfunction "G_1") (pintype "passive"))
    )
    (net (code "47") (name "Net-(T4-G)") (class "Default")
      (node (ref "D3") (pin "C") (pinfunction "C_C") (pintype "passive"))
      (node (ref "R19") (pin "1") (pinfunction "1_1") (pintype "passive"))
      (node (ref "R20") (pin "1") (pinfunction "1_1") (pintype "passive"))
      (node (ref "T4") (pin "1") (pinfunction "G_1") (pintype "passive"))
    )
    (net (code "48") (name "Net-(T5-G)") (class "Default")
      (node (ref "D8") (pin "A") (pinfunction "A_A") (pintype "passive"))
      (node (ref "D9") (pin "C") (pinfunction "C_C") (pintype "passive"))
      (node (ref "R15") (pin "2") (pinfunction "2_2") (pintype "passive"))
      (node (ref "R21") (pin "1") (pinfunction "1_1") (pintype "passive"))
      (node (ref "T5") (pin "1") (pinfunction "G_1") (pintype "passive"))
    )
    (net (code "49") (name "Net-(T6-DS1)") (class "Default")
      (node (ref "R21") (pin "2") (pinfunction "2_2") (pintype "passive"))
      (node (ref "T6") (pin "4") (pinfunction "DS1_4") (pintype "passive"))
    )
    (net (code "50") (name "Net-(T6-DS2)") (class "Default")
      (node (ref "R20") (pin "2") (pinfunction "2_2") (pintype "passive"))
      (node (ref "T6") (pin "6") (pinfunction "DS2_6") (pintype "passive"))
    )
  )
)
